# MASTER.net
KiCad netlist of a schematic drawn in Altium Designer
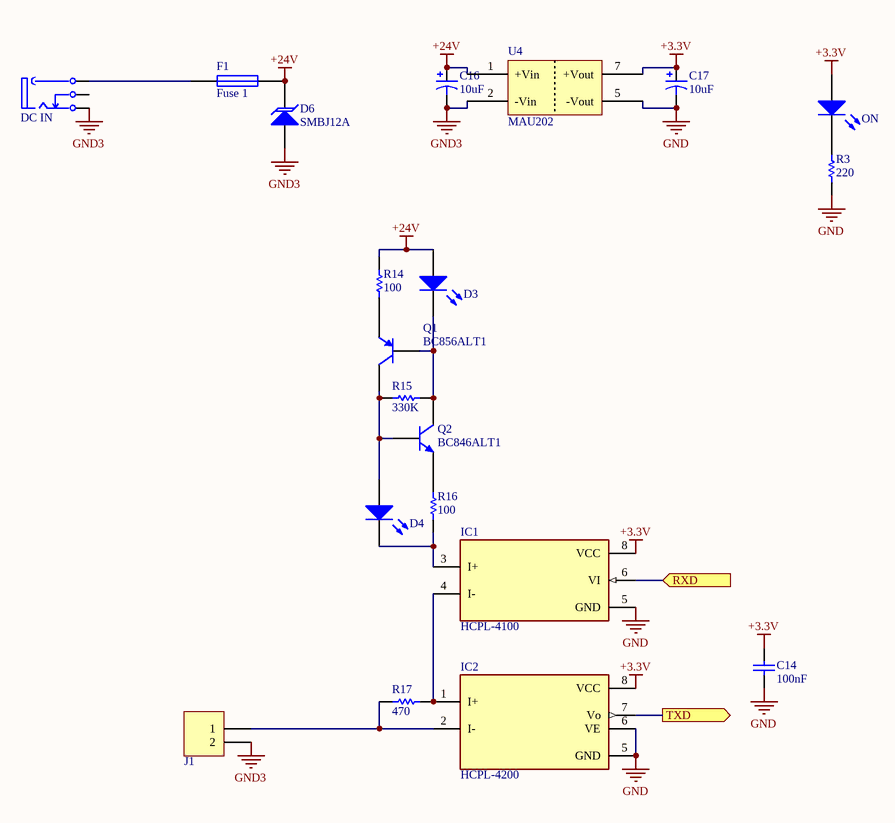
[diagram p0: MASTER.SchDoc]

(export (version "E")
  (design (tool "Eeschema 10.0.6"))
  (components
    (comp (ref "C14")
      (value "100nF")
      (footprint "C603")
      (description "Capacitor")
      (fields (field (name "DESIGNER") "Parsa Malekpour"))
      (libsource (lib "ParsaLibrary") (part "Cap"))
    )
    (comp (ref "C16")
      (value "10uF")
      (footprint "CAP-TAN-B")
      (description "Polar Capacitor")
      (fields (field (name "VOLTAGE") "10V"))
      (libsource (lib "ParsaLibrary") (part "CAP-POL"))
    )
    (comp (ref "C17")
      (value "10uF")
      (footprint "CAP-TAN-B")
      (description "Polar Capacitor")
      (fields (field (name "VOLTAGE") "10V"))
      (libsource (lib "ParsaLibrary") (part "CAP-POL"))
    )
    (comp (ref "D3") (value "LED") (footprint "LED-1206") (libsource (lib "ParsaLibrary") (part "LED")))
    (comp (ref "D4") (value "LED") (footprint "LED-1206") (libsource (lib "ParsaLibrary") (part "LED")))
    (comp (ref "D6")
      (value "SMBJ12A")
      (footprint "DO-214AA")
      (description "Surface Mount Transient Voltage Suppressors Diode")
      (libsource (lib "ParsaLibrary") (part "SMBJxxA"))
    )
    (comp (ref "DC IN")
      (value "JACK")
      (footprint "jack-dc")
      (libsource (lib "ParsaLibrary") (part "JACK-DC"))
    )
    (comp (ref "F1")
      (value "Fuse 1")
      (footprint "PTC-0805")
      (description "Fuse")
      (fields (field (name "PUBLISHER") "Altium Limited"))
      (libsource (lib "Miscellaneous Devices") (part "Fuse 1"))
    )
    (comp (ref "IC1")
      (value "HCPL-4100")
      (footprint "PARSALIBRARY:DIP-8")
      (description "<b>Isolation Amplifer</b><p> Source: http://www.avagotech.com/docs/AV02-0410EN")
      (fields (field (name "MF") "{'manufacturer': u'Broadcom Limited'}"))
      (libsource (lib "ParsaLibrary") (part "HCPL-4100"))
    )
    (comp (ref "IC2")
      (value "HCPL-4200")
      (footprint "PARSALIBRARY:DIP-8")
      (description "Optically Coupled 20 mA Current Loop Receiver")
      (fields (field (name "MF") "{'manufacturer': u'Broadcom Limited'}") (field (name "MP") "HCPL-4100"))
      (libsource (lib "ParsaLibrary") (part "HCPL-4200"))
    )
    (comp (ref "J1") (value "CONN-2") (footprint "XH-2") (libsource (lib "ParsaLibrary") (part "CONN-2")))
    (comp (ref "ON") (value "LED") (footprint "LED-1206") (libsource (lib "ParsaLibrary") (part "LED")))
    (comp (ref "Q1")
      (value "BC856ALT1")
      (footprint "SOT-23")
      (description "General Purpose Transistor PNP Silicon")
      (fields (field (name "PUBLISHER") "Altium Limited"))
      (libsource (lib "Motorola Discrete BJT") (part "BC856ALT1"))
    )
    (comp (ref "Q2")
      (value "BC846ALT1")
      (footprint "SOT-23")
      (description "General Purpose Transistor NPN Silicon")
      (fields (field (name "PUBLISHER") "Altium Limited"))
      (libsource (lib "Motorola Discrete BJT") (part "BC846ALT1"))
    )
    (comp (ref "R3")
      (value "220")
      (footprint "R805")
      (description "Resistor")
      (fields (field (name "DESIGNER") "Parsa Malekpour"))
      (libsource (lib "ParsaLibrary") (part "Resistor"))
    )
    (comp (ref "R14")
      (value "100")
      (footprint "R805")
      (description "Resistor")
      (fields (field (name "DESIGNER") "Parsa Malekpour"))
      (libsource (lib "ParsaLibrary") (part "Resistor"))
    )
    (comp (ref "R15")
      (value "330K")
      (footprint "R805")
      (description "Resistor")
      (fields (field (name "DESIGNER") "Parsa Malekpour"))
      (libsource (lib "ParsaLibrary") (part "Resistor"))
    )
    (comp (ref "R16")
      (value "100")
      (footprint "R805")
      (description "Resistor")
      (fields (field (name "DESIGNER") "Parsa Malekpour"))
      (libsource (lib "ParsaLibrary") (part "Resistor"))
    )
    (comp (ref "R17")
      (value "470")
      (footprint "R805")
      (description "Resistor")
      (fields (field (name "DESIGNER") "Parsa Malekpour"))
      (libsource (lib "ParsaLibrary") (part "Resistor"))
    )
    (comp (ref "U4")
      (value "MAU202")
      (footprint "MAU202")
      (description "1W, FIXED INPUT ISOLATED & UNREGULATED\r\nSINGLE OUTPUT DC-DC CONVERTER")
      (libsource (lib "ParsaLibrary") (part "MAU202"))
    )
  )
  (nets
    (net (code "1") (name "+3.3V") (class "Default")
      (node (ref "C14") (pin "2") (pinfunction "2_2") (pintype "passive"))
      (node (ref "C17") (pin "1") (pinfunction "1_1") (pintype "passive"))
      (node (ref "IC1") (pin "8") (pinfunction "VCC_8") (pintype "power_in"))
      (node (ref "IC2") (pin "8") (pinfunction "VCC_8") (pintype "power_in"))
      (node (ref "ON") (pin "1") (pinfunction "A_1") (pintype "passive"))
      (node (ref "U4") (pin "7") (pinfunction "+Vout_7") (pintype "passive"))
    )
    (net (code "2") (name "+24V") (class "Default")
      (node (ref "C16") (pin "1") (pinfunction "1_1") (pintype "passive"))
      (node (ref "D3") (pin "1") (pinfunction "A_1") (pintype "passive"))
      (node (ref "D6") (pin "2") (pinfunction "K_2") (pintype "passive"))
      (node (ref "F1") (pin "2") (pinfunction "2_2") (pintype "passive"))
      (node (ref "R14") (pin "2") (pinfunction "2_2") (pintype "passive"))
      (node (ref "U4") (pin "1") (pinfunction "+Vin_1") (pintype "passive"))
    )
    (net (code "3") (name "/RXD") (class "Default")
      (node (ref "IC1") (pin "6") (pinfunction "VI_6") (pintype "input"))
    )
    (net (code "4") (name "/TXD") (class "Default")
      (node (ref "IC2") (pin "7") (pinfunction "Vo_7") (pintype "output"))
    )
    (net (code "5") (name "GND") (class "Default")
      (node (ref "C14") (pin "1") (pinfunction "1_1") (pintype "passive"))
      (node (ref "C17") (pin "2") (pinfunction "2_2") (pintype "passive"))
      (node (ref "IC1") (pin "5") (pinfunction "GND_5") (pintype "power_in"))
      (node (ref "IC2") (pin "5") (pinfunction "GND_5") (pintype "power_in"))
      (node (ref "IC2") (pin "6") (pinfunction "VE_6") (pintype "power_in"))
      (node (ref "R3") (pin "1") (pinfunction "1_1") (pintype "passive"))
      (node (ref "U4") (pin "5") (pinfunction "-Vout_5") (pintype "passive"))
    )
    (net (code "6") (name "GND3") (class "Default")
      (node (ref "C16") (pin "2") (pinfunction "2_2") (pintype "passive"))
      (node (ref "D6") (pin "1") (pinfunction "A_1") (pintype "passive"))
      (node (ref "DC IN") (pin "3") (pinfunction "sleeve_3") (pintype "power_in"))
      (node (ref "J1") (pin "2") (pinfunction "2_2") (pintype "passive"))
      (node (ref "U4") (pin "2") (pinfunction "-Vin_2") (pintype "passive"))
    )
    (net (code "7") (name "Net-(D3-K)") (class "Default")
      (node (ref "D3") (pin "2") (pinfunction "K_2") (pintype "passive"))
      (node (ref "Q1") (pin "1") (pinfunction "B_1") (pintype "passive"))
      (node (ref "Q2") (pin "3") (pinfunction "C_3") (pintype "passive"))
      (node (ref "R15") (pin "1") (pinfunction "1_1") (pintype "passive"))
    )
    (net (code "8") (name "Net-(D4-A)") (class "Default")
      (node (ref "D4") (pin "1") (pinfunction "A_1") (pintype "passive"))
      (node (ref "Q1") (pin "3") (pinfunction "C_3") (pintype "passive"))
      (node (ref "Q2") (pin "1") (pinfunction "B_1") (pintype "passive"))
      (node (ref "R15") (pin "2") (pinfunction "2_2") (pintype "passive"))
    )
    (net (code "9") (name "Net-(D4-K)") (class "Default")
      (node (ref "D4") (pin "2") (pinfunction "K_2") (pintype "passive"))
      (node (ref "IC1") (pin "3") (pinfunction "I+_3") (pintype "power_in"))
      (node (ref "R16") (pin "1") (pinfunction "1_1") (pintype "passive"))
    )
    (net (code "10") (name "Net-(DC IN-tip)") (class "Default")
      (node (ref "DC IN") (pin "2") (pinfunction "tip_2") (pintype "power_in"))
      (node (ref "F1") (pin "1") (pinfunction "1_1") (pintype "passive"))
    )
    (net (code "11") (name "Net-(IC1-I-)") (class "Default")
      (node (ref "IC1") (pin "4") (pinfunction "I-_4") (pintype "power_in"))
      (node (ref "IC2") (pin "1") (pinfunction "I+_1") (pintype "power_in"))
      (node (ref "R17") (pin "2") (pinfunction "2_2") (pintype "passive"))
    )
    (net (code "12") (name "Net-(IC2-I-)") (class "Default")
      (node (ref "IC2") (pin "2") (pinfunction "I-_2") (pintype "power_in"))
      (node (ref "J1") (pin "1") (pinfunction "1_1") (pintype "passive"))
      (node (ref "R17") (pin "1") (pinfunction "1_1") (pintype "passive"))
    )
    (net (code "13") (name "Net-(ON-K)") (class "Default")
      (node (ref "ON") (pin "2") (pinfunction "K_2") (pintype "passive"))
      (node (ref "R3") (pin "2") (pinfunction "2_2") (pintype "passive"))
    )
    (net (code "14") (name "Net-(Q1-E)") (class "Default")
      (node (ref "Q1") (pin "2") (pinfunction "E_2") (pintype "passive"))
      (node (ref "R14") (pin "1") (pinfunction "1_1") (pintype "passive"))
    )
    (net (code "15") (name "Net-(Q2-E)") (class "Default")
      (node (ref "Q2") (pin "2") (pinfunction "E_2") (pintype "passive"))
      (node (ref "R16") (pin "2") (pinfunction "2_2") (pintype "passive"))
    )
    (net (code "16") (name "unconnected-(DC IN-det-Pad1)") (class "Default")
      (node (ref "DC IN") (pin "1") (pinfunction "det_1") (pintype "passive"))
    )
  )
)
